# xPi.net
KiCad netlist of a schematic drawn in EAGLE
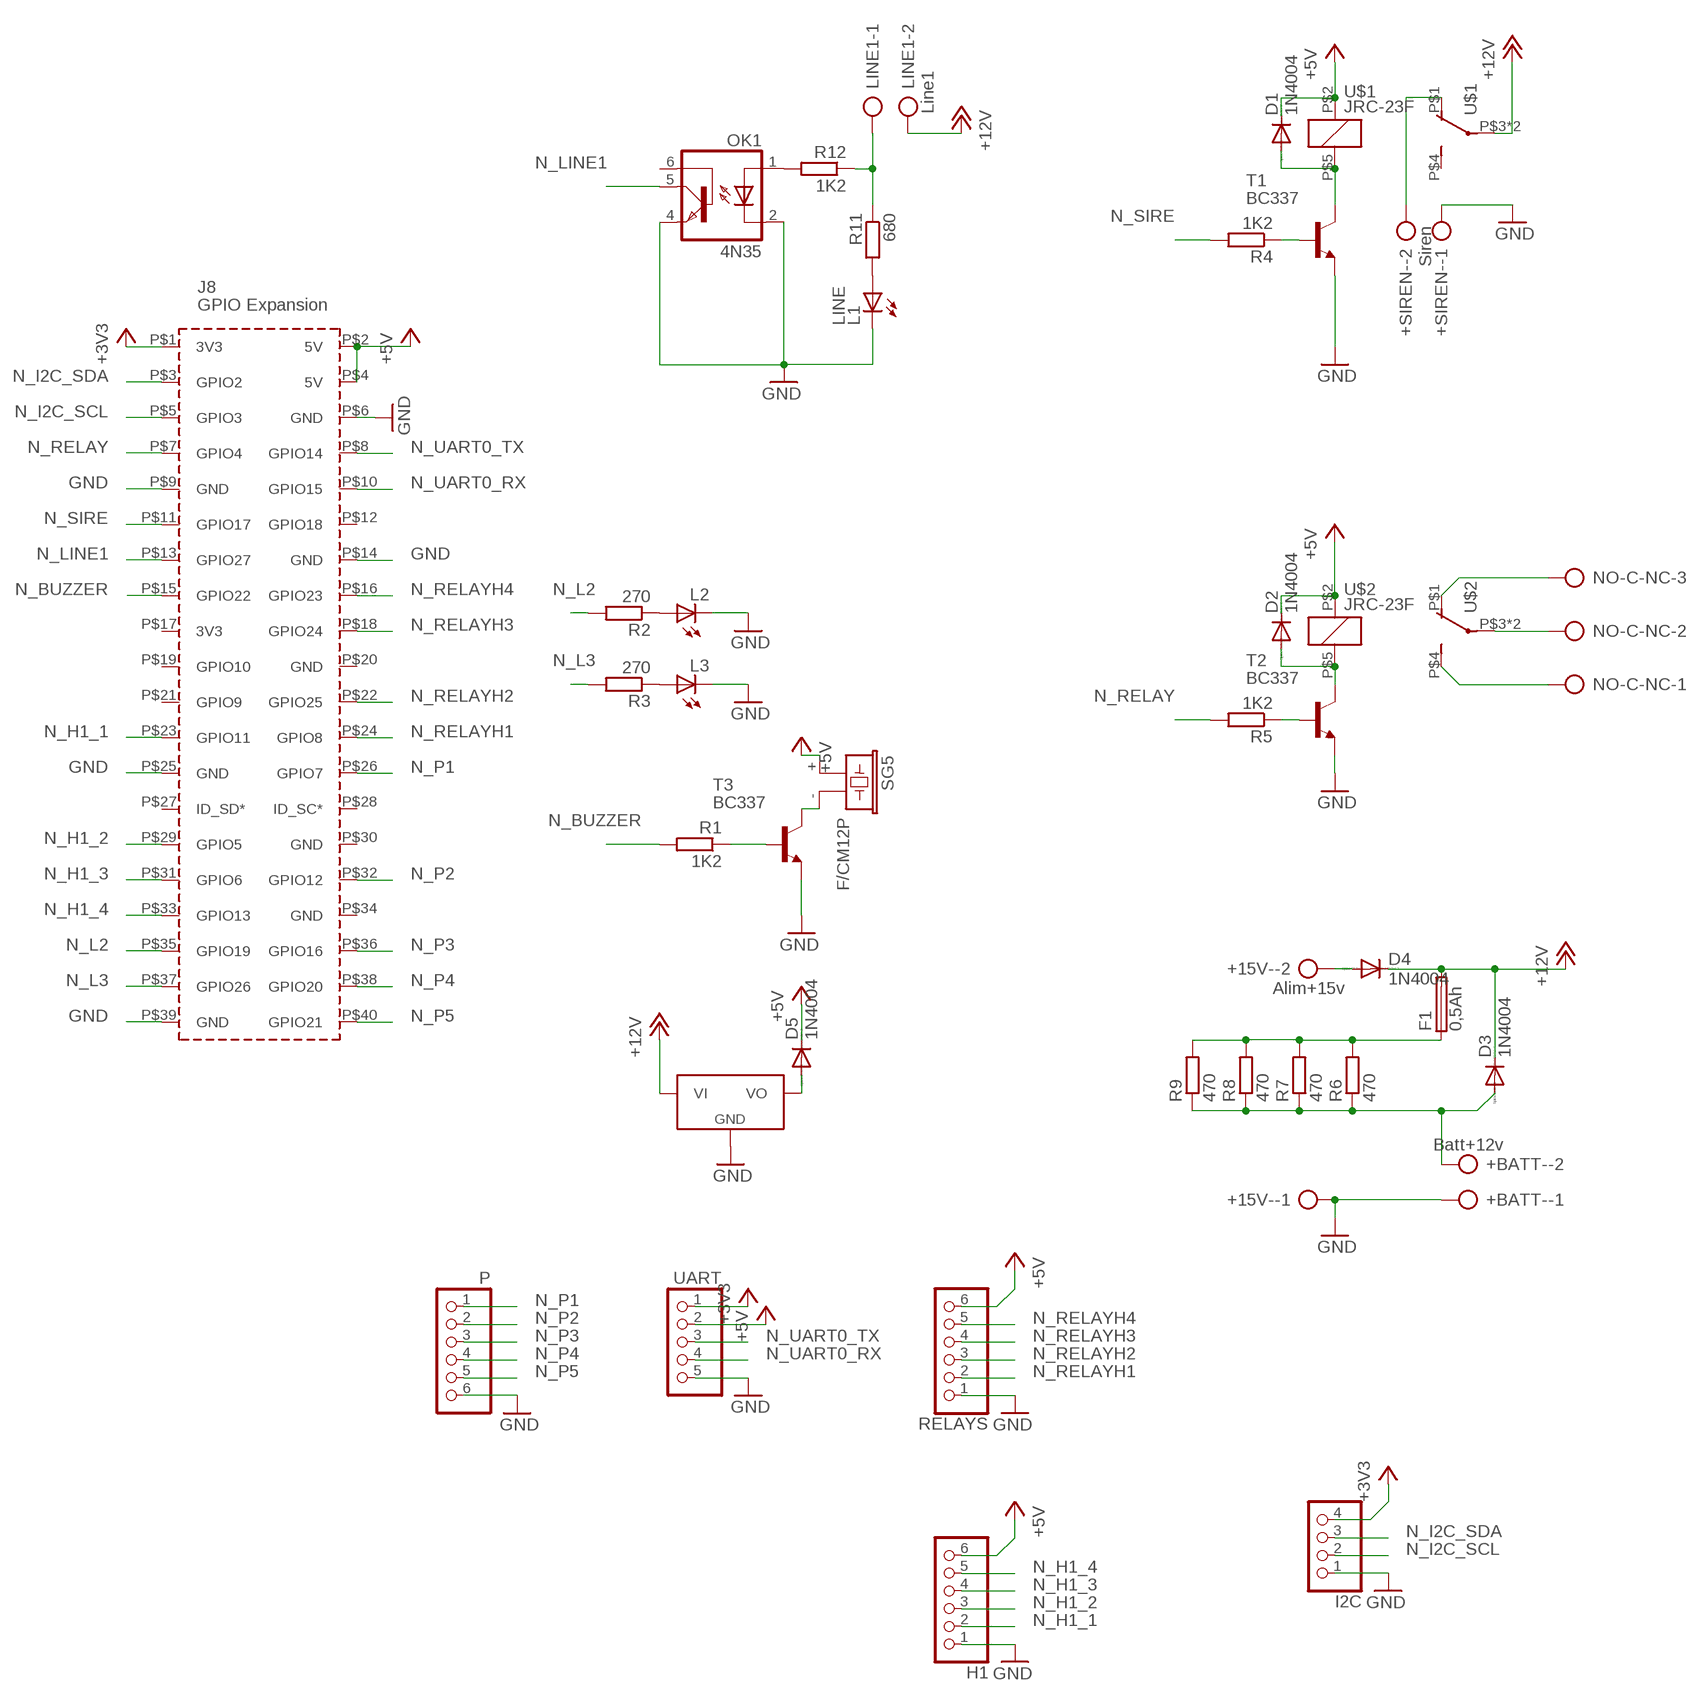
[diagram p0: schematic, sheet 1]

(export (version "E")
  (design (tool "Eeschema 10.0.6"))
  (components
    (comp (ref "+15V-")
      (value "Alim+15v")
      (footprint "eagle-import:AK300_2")
      (libsource (lib "eagle-import") (part "AK300/2"))
    )
    (comp (ref "+BATT-")
      (value "Batt+12v")
      (footprint "eagle-import:AK300_2")
      (libsource (lib "eagle-import") (part "AK300/2"))
    )
    (comp (ref "+SIREN-")
      (value "Siren")
      (footprint "eagle-import:AK300_2")
      (libsource (lib "eagle-import") (part "AK300/2"))
    )
    (comp (ref "D1")
      (value "1N4004")
      (footprint "eagle-import:DO41-10")
      (libsource (lib "eagle-import") (part "1N4004"))
    )
    (comp (ref "D2")
      (value "1N4004")
      (footprint "eagle-import:DO41-10")
      (libsource (lib "eagle-import") (part "1N4004"))
    )
    (comp (ref "D3")
      (value "1N4004")
      (footprint "eagle-import:DO41-10")
      (libsource (lib "eagle-import") (part "1N4004"))
    )
    (comp (ref "D4")
      (value "1N4004")
      (footprint "eagle-import:DO41-10")
      (libsource (lib "eagle-import") (part "1N4004"))
    )
    (comp (ref "D5")
      (value "1N4004")
      (footprint "eagle-import:DO41-10")
      (libsource (lib "eagle-import") (part "1N4004"))
    )
    (comp (ref "F1")
      (value "0,5Ah")
      (footprint "eagle-import:KS9V")
      (libsource (lib "eagle-import") (part "FUSEKS9V"))
    )
    (comp (ref "H1")
      (value "PINHD-1X6")
      (footprint "eagle-import:1X06")
      (libsource (lib "eagle-import") (part "PINHD-1X6"))
    )
    (comp (ref "I2C")
      (value "PINHD-1X4")
      (footprint "eagle-import:1X04")
      (libsource (lib "eagle-import") (part "PINHD-1X4"))
    )
    (comp (ref "L1")
      (value "LINE")
      (footprint "eagle-import:LED3MM")
      (libsource (lib "eagle-import") (part "LED3MM"))
    )
    (comp (ref "L2")
      (value "LED3MM")
      (footprint "eagle-import:LED3MM")
      (libsource (lib "eagle-import") (part "LED3MM"))
    )
    (comp (ref "L3")
      (value "LED3MM")
      (footprint "eagle-import:LED3MM")
      (libsource (lib "eagle-import") (part "LED3MM"))
    )
    (comp (ref "LINE1")
      (value "Line1")
      (footprint "eagle-import:AK300_2")
      (libsource (lib "eagle-import") (part "AK300/2"))
    )
    (comp (ref "NO-C-NC")
      (value "AK300/3")
      (footprint "eagle-import:AK300_3")
      (libsource (lib "eagle-import") (part "AK300/3"))
    )
    (comp (ref "OK1")
      (value "4N35")
      (footprint "eagle-import:DIL06")
      (fields (field (name "MF") "FAIRCHILD SEMICONDUCTOR"))
      (libsource (lib "eagle-import") (part "4N35"))
    )
    (comp (ref "P")
      (value "PINHD-1X6")
      (footprint "eagle-import:1X06")
      (libsource (lib "eagle-import") (part "PINHD-1X6"))
    )
    (comp (ref "R1")
      (value "1K2")
      (footprint "eagle-import:0204_7")
      (libsource (lib "eagle-import") (part "resistor_348_R-EU_0204/7"))
    )
    (comp (ref "R2")
      (value "270")
      (footprint "eagle-import:0204_7")
      (libsource (lib "eagle-import") (part "resistor_348_R-EU_0204/7"))
    )
    (comp (ref "R3")
      (value "270")
      (footprint "eagle-import:0204_7")
      (libsource (lib "eagle-import") (part "resistor_348_R-EU_0204/7"))
    )
    (comp (ref "R4")
      (value "1K2")
      (footprint "eagle-import:0204V")
      (libsource (lib "eagle-import") (part "resistor_348_R-EU_0204/2V"))
    )
    (comp (ref "R5")
      (value "1K2")
      (footprint "eagle-import:0204V")
      (libsource (lib "eagle-import") (part "resistor_348_R-EU_0204/2V"))
    )
    (comp (ref "R6")
      (value "470")
      (footprint "eagle-import:0204_7")
      (libsource (lib "eagle-import") (part "R-EU_0204/7"))
    )
    (comp (ref "R7")
      (value "470")
      (footprint "eagle-import:0204_7")
      (libsource (lib "eagle-import") (part "R-EU_0204/7"))
    )
    (comp (ref "R8")
      (value "470")
      (footprint "eagle-import:0204_7")
      (libsource (lib "eagle-import") (part "R-EU_0204/7"))
    )
    (comp (ref "R9")
      (value "470")
      (footprint "eagle-import:0204_7")
      (libsource (lib "eagle-import") (part "R-EU_0204/7"))
    )
    (comp (ref "R11")
      (value "680")
      (footprint "eagle-import:0204_7")
      (libsource (lib "eagle-import") (part "resistor_348_R-EU_0204/7"))
    )
    (comp (ref "R12")
      (value "1K2")
      (footprint "eagle-import:0204_7")
      (libsource (lib "eagle-import") (part "resistor_348_R-EU_0204/7"))
    )
    (comp (ref "RELAYS")
      (value "PINHD-1X6")
      (footprint "eagle-import:1X06")
      (libsource (lib "eagle-import") (part "PINHD-1X6"))
    )
    (comp (ref "SG5")
      (value "F/CM12P")
      (footprint "eagle-import:F_CM12P")
      (libsource (lib "eagle-import") (part "F/CM12P"))
    )
    (comp (ref "T1")
      (value "BC337")
      (footprint "eagle-import:TO92")
      (libsource (lib "eagle-import") (part "BC337"))
    )
    (comp (ref "T2")
      (value "BC337")
      (footprint "eagle-import:TO92")
      (libsource (lib "eagle-import") (part "BC337"))
    )
    (comp (ref "T3")
      (value "BC337")
      (footprint "eagle-import:TO92")
      (libsource (lib "eagle-import") (part "BC337"))
    )
    (comp (ref "U$1")
      (value "JRC-23F")
      (footprint "eagle-import:JRC-23F")
      (libsource (lib "eagle-import") (part "JRC-23F"))
    )
    (comp (ref "U$2")
      (value "JRC-23F")
      (footprint "eagle-import:JRC-23F")
      (libsource (lib "eagle-import") (part "JRC-23F"))
    )
    (comp (ref "U$5")
      (value "DSWY2596")
      (footprint "eagle-import:DSWY2596")
      (libsource (lib "eagle-import") (part "DSWY2596"))
    )
    (comp (ref "U$6")
      (value "RPI3_2")
      (footprint "eagle-import:RPI3_2")
      (libsource (lib "eagle-import") (part "RPI3_2"))
    )
    (comp (ref "UART")
      (value "PINHD-1X5")
      (footprint "eagle-import:1X05")
      (libsource (lib "eagle-import") (part "PINHD-1X5"))
    )
  )
  (nets
    (net (code "1") (name "+3V3") (class "Default")
      (node (ref "I2C") (pin "4") (pinfunction "4_4") (pintype "passive"))
      (node (ref "U$6") (pin "P$1") (pinfunction "3V3_P$1") (pintype "bidirectional"))
      (node (ref "UART") (pin "1") (pinfunction "1_1") (pintype "passive"))
    )
    (net (code "2") (name "+5V") (class "Default")
      (node (ref "D1") (pin "C") (pinfunction "C_C") (pintype "passive"))
      (node (ref "D2") (pin "C") (pinfunction "C_C") (pintype "passive"))
      (node (ref "D5") (pin "C") (pinfunction "C_C") (pintype "passive"))
      (node (ref "H1") (pin "6") (pinfunction "6_6") (pintype "passive"))
      (node (ref "RELAYS") (pin "6") (pinfunction "6_6") (pintype "passive"))
      (node (ref "SG5") (pin "+") (pinfunction "1_+") (pintype "passive"))
      (node (ref "U$1") (pin "P$2") (pinfunction "1_P$2") (pintype "passive"))
      (node (ref "U$2") (pin "P$2") (pinfunction "1_P$2") (pintype "passive"))
      (node (ref "U$6") (pin "P$2") (pinfunction "5V_P$2") (pintype "bidirectional"))
      (node (ref "U$6") (pin "P$4") (pinfunction "5V_P$4") (pintype "bidirectional"))
      (node (ref "UART") (pin "2") (pinfunction "2_2") (pintype "passive"))
    )
    (net (code "3") (name "+12V") (class "Default")
      (node (ref "D3") (pin "C") (pinfunction "C_C") (pintype "passive"))
      (node (ref "D4") (pin "C") (pinfunction "C_C") (pintype "passive"))
      (node (ref "F1") (pin "2") (pinfunction "2_2") (pintype "passive"))
      (node (ref "LINE1") (pin "2") (pinfunction "KL_2") (pintype "passive"))
      (node (ref "U$1") (pin "P$3") (pinfunction "P_P$3") (pintype "passive"))
      (node (ref "U$1") (pin "P$6") (pinfunction "P_P$6") (pintype "passive"))
      (node (ref "U$5") (pin "VI") (pinfunction "VI_VI") (pintype "passive"))
    )
    (net (code "4") (name "/N_BUZZER") (class "Default")
      (node (ref "R1") (pin "2") (pinfunction "2_2") (pintype "passive"))
      (node (ref "U$6") (pin "P$15") (pinfunction "GPIO22_P$15") (pintype "bidirectional"))
    )
    (net (code "5") (name "/N_H1_1") (class "Default")
      (node (ref "H1") (pin "2") (pinfunction "2_2") (pintype "passive"))
      (node (ref "U$6") (pin "P$23") (pinfunction "GPIO11_P$23") (pintype "bidirectional"))
    )
    (net (code "6") (name "/N_H1_2") (class "Default")
      (node (ref "H1") (pin "3") (pinfunction "3_3") (pintype "passive"))
      (node (ref "U$6") (pin "P$29") (pinfunction "GPIO5_P$29") (pintype "bidirectional"))
    )
    (net (code "7") (name "/N_H1_3") (class "Default")
      (node (ref "H1") (pin "4") (pinfunction "4_4") (pintype "passive"))
      (node (ref "U$6") (pin "P$31") (pinfunction "GPIO6_P$31") (pintype "bidirectional"))
    )
    (net (code "8") (name "/N_H1_4") (class "Default")
      (node (ref "H1") (pin "5") (pinfunction "5_5") (pintype "passive"))
      (node (ref "U$6") (pin "P$33") (pinfunction "GPIO13_P$33") (pintype "bidirectional"))
    )
    (net (code "9") (name "/N_I2C_SCL") (class "Default")
      (node (ref "I2C") (pin "2") (pinfunction "2_2") (pintype "passive"))
      (node (ref "U$6") (pin "P$5") (pinfunction "GPIO3_P$5") (pintype "bidirectional"))
    )
    (net (code "10") (name "/N_I2C_SDA") (class "Default")
      (node (ref "I2C") (pin "3") (pinfunction "3_3") (pintype "passive"))
      (node (ref "U$6") (pin "P$3") (pinfunction "GPIO2_P$3") (pintype "bidirectional"))
    )
    (net (code "11") (name "/N_L2") (class "Default")
      (node (ref "R2") (pin "2") (pinfunction "2_2") (pintype "passive"))
      (node (ref "U$6") (pin "P$35") (pinfunction "GPIO19_P$35") (pintype "bidirectional"))
    )
    (net (code "12") (name "/N_L3") (class "Default")
      (node (ref "R3") (pin "2") (pinfunction "2_2") (pintype "passive"))
      (node (ref "U$6") (pin "P$37") (pinfunction "GPIO26_P$37") (pintype "bidirectional"))
    )
    (net (code "13") (name "/N_LINE1") (class "Default")
      (node (ref "OK1") (pin "5") (pinfunction "COL_5") (pintype "passive"))
      (node (ref "U$6") (pin "P$13") (pinfunction "GPIO27_P$13") (pintype "bidirectional"))
    )
    (net (code "14") (name "/N_P1") (class "Default")
      (node (ref "P") (pin "1") (pinfunction "1_1") (pintype "passive"))
      (node (ref "U$6") (pin "P$26") (pinfunction "GPIO7_P$26") (pintype "bidirectional"))
    )
    (net (code "15") (name "/N_P2") (class "Default")
      (node (ref "P") (pin "2") (pinfunction "2_2") (pintype "passive"))
      (node (ref "U$6") (pin "P$32") (pinfunction "GPIO12_P$32") (pintype "bidirectional"))
    )
    (net (code "16") (name "/N_P3") (class "Default")
      (node (ref "P") (pin "3") (pinfunction "3_3") (pintype "passive"))
      (node (ref "U$6") (pin "P$36") (pinfunction "GPIO16_P$36") (pintype "bidirectional"))
    )
    (net (code "17") (name "/N_P4") (class "Default")
      (node (ref "P") (pin "4") (pinfunction "4_4") (pintype "passive"))
      (node (ref "U$6") (pin "P$38") (pinfunction "GPIO20_P$38") (pintype "bidirectional"))
    )
    (net (code "18") (name "/N_P5") (class "Default")
      (node (ref "P") (pin "5") (pinfunction "5_5") (pintype "passive"))
      (node (ref "U$6") (pin "P$40") (pinfunction "GPIO21_P$40") (pintype "bidirectional"))
    )
    (net (code "19") (name "/N_RELAY") (class "Default")
      (node (ref "R5") (pin "2") (pinfunction "2_2") (pintype "passive"))
      (node (ref "U$6") (pin "P$7") (pinfunction "GPIO4_P$7") (pintype "bidirectional"))
    )
    (net (code "20") (name "/N_RELAYH1") (class "Default")
      (node (ref "RELAYS") (pin "2") (pinfunction "2_2") (pintype "passive"))
      (node (ref "U$6") (pin "P$24") (pinfunction "GPIO8_P$24") (pintype "bidirectional"))
    )
    (net (code "21") (name "/N_RELAYH2") (class "Default")
      (node (ref "RELAYS") (pin "3") (pinfunction "3_3") (pintype "passive"))
      (node (ref "U$6") (pin "P$22") (pinfunction "GPIO25_P$22") (pintype "bidirectional"))
    )
    (net (code "22") (name "/N_RELAYH3") (class "Default")
      (node (ref "RELAYS") (pin "4") (pinfunction "4_4") (pintype "passive"))
      (node (ref "U$6") (pin "P$18") (pinfunction "GPIO24_P$18") (pintype "bidirectional"))
    )
    (net (code "23") (name "/N_RELAYH4") (class "Default")
      (node (ref "RELAYS") (pin "5") (pinfunction "5_5") (pintype "passive"))
      (node (ref "U$6") (pin "P$16") (pinfunction "GPIO23_P$16") (pintype "bidirectional"))
    )
    (net (code "24") (name "/N_SIRE") (class "Default")
      (node (ref "R4") (pin "2") (pinfunction "2_2") (pintype "passive"))
      (node (ref "U$6") (pin "P$11") (pinfunction "GPIO17_P$11") (pintype "bidirectional"))
    )
    (net (code "25") (name "/N_UART0_RX") (class "Default")
      (node (ref "U$6") (pin "P$10") (pinfunction "GPIO15_P$10") (pintype "bidirectional"))
      (node (ref "UART") (pin "4") (pinfunction "4_4") (pintype "passive"))
    )
    (net (code "26") (name "/N_UART0_TX") (class "Default")
      (node (ref "U$6") (pin "P$8") (pinfunction "GPIO14_P$8") (pintype "bidirectional"))
      (node (ref "UART") (pin "3") (pinfunction "3_3") (pintype "passive"))
    )
    (net (code "27") (name "GND") (class "Default")
      (node (ref "+15V-") (pin "1") (pinfunction "KL_1") (pintype "passive"))
      (node (ref "+BATT-") (pin "1") (pinfunction "KL_1") (pintype "passive"))
      (node (ref "+SIREN-") (pin "1") (pinfunction "KL_1") (pintype "passive"))
      (node (ref "H1") (pin "1") (pinfunction "1_1") (pintype "passive"))
      (node (ref "I2C") (pin "1") (pinfunction "1_1") (pintype "passive"))
      (node (ref "L1") (pin "K") (pinfunction "C_K") (pintype "passive"))
      (node (ref "L2") (pin "K") (pinfunction "C_K") (pintype "passive"))
      (node (ref "L3") (pin "K") (pinfunction "C_K") (pintype "passive"))
      (node (ref "OK1") (pin "2") (pinfunction "C_2") (pintype "passive"))
      (node (ref "OK1") (pin "4") (pinfunction "EMI_4") (pintype "passive"))
      (node (ref "P") (pin "6") (pinfunction "6_6") (pintype "passive"))
      (node (ref "RELAYS") (pin "1") (pinfunction "1_1") (pintype "passive"))
      (node (ref "T1") (pin "1") (pinfunction "E_1") (pintype "passive"))
      (node (ref "T2") (pin "1") (pinfunction "E_1") (pintype "passive"))
      (node (ref "T3") (pin "1") (pinfunction "E_1") (pintype "passive"))
      (node (ref "U$5") (pin "GNDI") (pinfunction "GND_GNDI") (pintype "passive"))
      (node (ref "U$5") (pin "GNDO") (pinfunction "GND_GNDO") (pintype "passive"))
      (node (ref "U$6") (pin "P$14") (pinfunction "GND_P$14") (pintype "bidirectional"))
      (node (ref "U$6") (pin "P$25") (pinfunction "GND_P$25") (pintype "bidirectional"))
      (node (ref "U$6") (pin "P$39") (pinfunction "GND_P$39") (pintype "bidirectional"))
      (node (ref "U$6") (pin "P$6") (pinfunction "GND_P$6") (pintype "bidirectional"))
      (node (ref "U$6") (pin "P$9") (pinfunction "GND_P$9") (pintype "bidirectional"))
      (node (ref "UART") (pin "5") (pinfunction "5_5") (pintype "passive"))
    )
    (net (code "28") (name "Net-(+15V-B-KL)") (class "Default")
      (node (ref "+15V-") (pin "2") (pinfunction "KL_2") (pintype "passive"))
      (node (ref "D4") (pin "A") (pinfunction "A_A") (pintype "passive"))
    )
    (net (code "29") (name "Net-(+BATT-B-KL)") (class "Default")
      (node (ref "+BATT-") (pin "2") (pinfunction "KL_2") (pintype "passive"))
      (node (ref "D3") (pin "A") (pinfunction "A_A") (pintype "passive"))
      (node (ref "R6") (pin "1") (pinfunction "1_1") (pintype "passive"))
      (node (ref "R7") (pin "1") (pinfunction "1_1") (pintype "passive"))
      (node (ref "R8") (pin "1") (pinfunction "1_1") (pintype "passive"))
      (node (ref "R9") (pin "1") (pinfunction "1_1") (pintype "passive"))
    )
    (net (code "30") (name "Net-(+SIREN-B-KL)") (class "Default")
      (node (ref "+SIREN-") (pin "2") (pinfunction "KL_2") (pintype "passive"))
      (node (ref "U$1") (pin "P$1") (pinfunction "O_P$1") (pintype "passive"))
    )
    (net (code "31") (name "Net-(D5-PadA)") (class "Default")
      (node (ref "D5") (pin "A") (pinfunction "A_A") (pintype "passive"))
      (node (ref "U$5") (pin "VO") (pinfunction "VO_VO") (pintype "passive"))
    )
    (net (code "32") (name "Net-(F1-Pad1)") (class "Default")
      (node (ref "F1") (pin "1") (pinfunction "1_1") (pintype "passive"))
      (node (ref "R6") (pin "2") (pinfunction "2_2") (pintype "passive"))
      (node (ref "R7") (pin "2") (pinfunction "2_2") (pintype "passive"))
      (node (ref "R8") (pin "2") (pinfunction "2_2") (pintype "passive"))
      (node (ref "R9") (pin "2") (pinfunction "2_2") (pintype "passive"))
    )
    (net (code "33") (name "Net-(L1-PadA)") (class "Default")
      (node (ref "L1") (pin "A") (pinfunction "A_A") (pintype "passive"))
      (node (ref "R11") (pin "2") (pinfunction "2_2") (pintype "passive"))
    )
    (net (code "34") (name "Net-(L2-PadA)") (class "Default")
      (node (ref "L2") (pin "A") (pinfunction "A_A") (pintype "passive"))
      (node (ref "R2") (pin "1") (pinfunction "1_1") (pintype "passive"))
    )
    (net (code "35") (name "Net-(L3-PadA)") (class "Default")
      (node (ref "L3") (pin "A") (pinfunction "A_A") (pintype "passive"))
      (node (ref "R3") (pin "1") (pinfunction "1_1") (pintype "passive"))
    )
    (net (code "36") (name "Net-(LINE1A-KL)") (class "Default")
      (node (ref "LINE1") (pin "1") (pinfunction "KL_1") (pintype "passive"))
      (node (ref "R11") (pin "1") (pinfunction "1_1") (pintype "passive"))
      (node (ref "R12") (pin "1") (pinfunction "1_1") (pintype "passive"))
    )
    (net (code "37") (name "Net-(NO-C-NCA-KL)") (class "Default")
      (node (ref "NO-C-NC") (pin "1") (pinfunction "KL_1") (pintype "passive"))
      (node (ref "U$2") (pin "P$4") (pinfunction "S_P$4") (pintype "passive"))
    )
    (net (code "38") (name "Net-(NO-C-NCB-KL)") (class "Default")
      (node (ref "NO-C-NC") (pin "2") (pinfunction "KL_2") (pintype "passive"))
      (node (ref "U$2") (pin "P$3") (pinfunction "P_P$3") (pintype "passive"))
      (node (ref "U$2") (pin "P$6") (pinfunction "P_P$6") (pintype "passive"))
    )
    (net (code "39") (name "Net-(NO-C-NCC-KL)") (class "Default")
      (node (ref "NO-C-NC") (pin "3") (pinfunction "KL_3") (pintype "passive"))
      (node (ref "U$2") (pin "P$1") (pinfunction "O_P$1") (pintype "passive"))
    )
    (net (code "40") (name "Net-(OK1-A)") (class "Default")
      (node (ref "OK1") (pin "1") (pinfunction "A_1") (pintype "passive"))
      (node (ref "R12") (pin "2") (pinfunction "2_2") (pintype "passive"))
    )
    (net (code "41") (name "Net-(SG5-2)") (class "Default")
      (node (ref "SG5") (pin "-") (pinfunction "2_-") (pintype "passive"))
      (node (ref "T3") (pin "3") (pinfunction "C_3") (pintype "passive"))
    )
    (net (code "42") (name "Net-(T1-B)") (class "Default")
      (node (ref "R4") (pin "1") (pinfunction "1_1") (pintype "passive"))
      (node (ref "T1") (pin "2") (pinfunction "B_2") (pintype "passive"))
    )
    (net (code "43") (name "Net-(T1-C)") (class "Default")
      (node (ref "D1") (pin "A") (pinfunction "A_A") (pintype "passive"))
      (node (ref "T1") (pin "3") (pinfunction "C_3") (pintype "passive"))
      (node (ref "U$1") (pin "P$5") (pinfunction "2_P$5") (pintype "passive"))
    )
    (net (code "44") (name "Net-(T2-B)") (class "Default")
      (node (ref "R5") (pin "1") (pinfunction "1_1") (pintype "passive"))
      (node (ref "T2") (pin "2") (pinfunction "B_2") (pintype "passive"))
    )
    (net (code "45") (name "Net-(T2-C)") (class "Default")
      (node (ref "D2") (pin "A") (pinfunction "A_A") (pintype "passive"))
      (node (ref "T2") (pin "3") (pinfunction "C_3") (pintype "passive"))
      (node (ref "U$2") (pin "P$5") (pinfunction "2_P$5") (pintype "passive"))
    )
    (net (code "46") (name "Net-(T3-B)") (class "Default")
      (node (ref "R1") (pin "1") (pinfunction "1_1") (pintype "passive"))
      (node (ref "T3") (pin "2") (pinfunction "B_2") (pintype "passive"))
    )
    (net (code "47") (name "unconnected-(OK1-BAS-Pad6)") (class "Default")
      (node (ref "OK1") (pin "6") (pinfunction "BAS_6") (pintype "passive"))
    )
    (net (code "48") (name "unconnected-(U$1-S-PadP$4)") (class "Default")
      (node (ref "U$1") (pin "P$4") (pinfunction "S_P$4") (pintype "passive"))
    )
    (net (code "49") (name "unconnected-(U$6-3V3-PadP$17)") (class "Default")
      (node (ref "U$6") (pin "P$17") (pinfunction "3V3_P$17") (pintype "bidirectional"))
    )
    (net (code "50") (name "unconnected-(U$6-GND-PadP$20)") (class "Default")
      (node (ref "U$6") (pin "P$20") (pinfunction "GND_P$20") (pintype "bidirectional"))
    )
    (net (code "51") (name "unconnected-(U$6-GND-PadP$30)") (class "Default")
      (node (ref "U$6") (pin "P$30") (pinfunction "GND_P$30") (pintype "bidirectional"))
    )
    (net (code "52") (name "unconnected-(U$6-GND-PadP$34)") (class "Default")
      (node (ref "U$6") (pin "P$34") (pinfunction "GND_P$34") (pintype "bidirectional"))
    )
    (net (code "53") (name "unconnected-(U$6-GPIO9-PadP$21)") (class "Default")
      (node (ref "U$6") (pin "P$21") (pinfunction "GPIO9_P$21") (pintype "bidirectional"))
    )
    (net (code "54") (name "unconnected-(U$6-GPIO10-PadP$19)") (class "Default")
      (node (ref "U$6") (pin "P$19") (pinfunction "GPIO10_P$19") (pintype "bidirectional"))
    )
    (net (code "55") (name "unconnected-(U$6-GPIO18-PadP$12)") (class "Default")
      (node (ref "U$6") (pin "P$12") (pinfunction "GPIO18_P$12") (pintype "bidirectional"))
    )
    (net (code "56") (name "unconnected-(U$6-ID_SC*-PadP$28)") (class "Default")
      (node (ref "U$6") (pin "P$28") (pinfunction "ID_SC*_P$28") (pintype "bidirectional"))
    )
    (net (code "57") (name "unconnected-(U$6-ID_SD*-PadP$27)") (class "Default")
      (node (ref "U$6") (pin "P$27") (pinfunction "ID_SD*_P$27") (pintype "bidirectional"))
    )
  )
)
